# V0_1.net
KiCad netlist of a schematic drawn in EAGLE
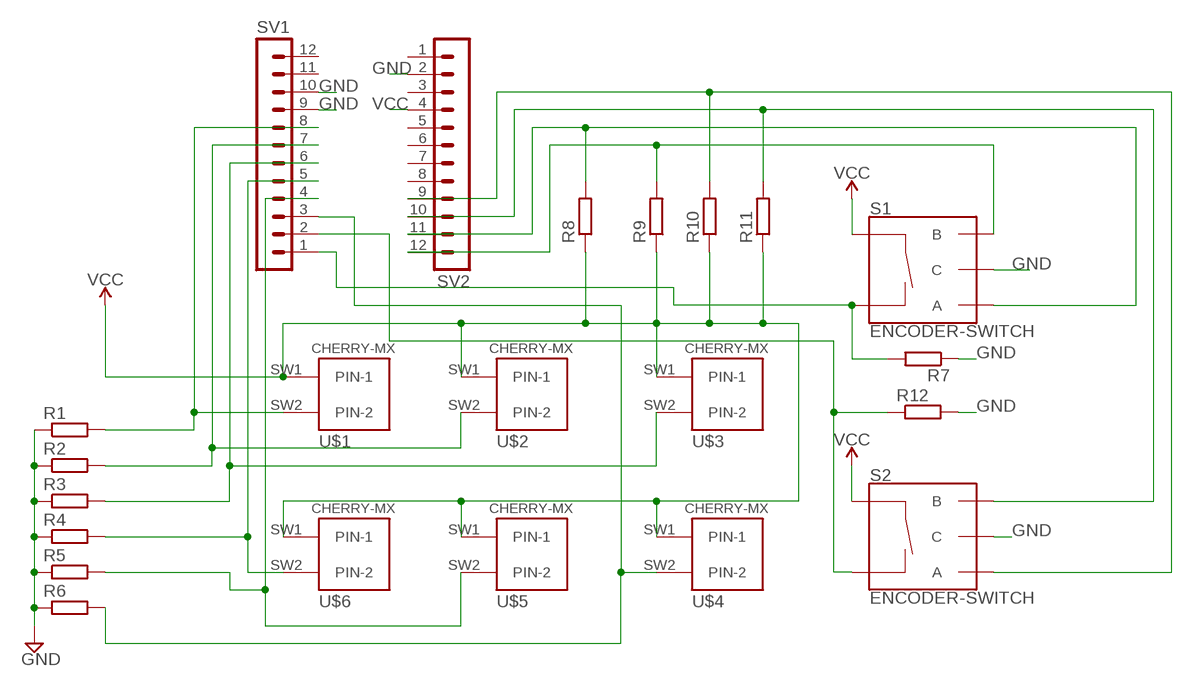
[diagram p0: schematic, sheet 1]

(export (version "E")
  (design (tool "Eeschema 10.0.6"))
  (components
    (comp (ref "R1")
      (value "R-EU_0207/10")
      (footprint "eagle-import:0207_10")
      (libsource (lib "eagle-import") (part "R-EU_0207/10"))
    )
    (comp (ref "R2")
      (value "R-EU_0207/10")
      (footprint "eagle-import:0207_10")
      (libsource (lib "eagle-import") (part "R-EU_0207/10"))
    )
    (comp (ref "R3")
      (value "R-EU_0207/10")
      (footprint "eagle-import:0207_10")
      (libsource (lib "eagle-import") (part "R-EU_0207/10"))
    )
    (comp (ref "R4")
      (value "R-EU_0207/10")
      (footprint "eagle-import:0207_10")
      (libsource (lib "eagle-import") (part "R-EU_0207/10"))
    )
    (comp (ref "R5")
      (value "R-EU_0207/10")
      (footprint "eagle-import:0207_10")
      (libsource (lib "eagle-import") (part "R-EU_0207/10"))
    )
    (comp (ref "R6")
      (value "R-EU_0207/10")
      (footprint "eagle-import:0207_10")
      (libsource (lib "eagle-import") (part "R-EU_0207/10"))
    )
    (comp (ref "R7")
      (value "R-EU_0207/10")
      (footprint "eagle-import:0207_10")
      (libsource (lib "eagle-import") (part "R-EU_0207/10"))
    )
    (comp (ref "R8")
      (value "R-EU_0207/10")
      (footprint "eagle-import:0207_10")
      (libsource (lib "eagle-import") (part "R-EU_0207/10"))
    )
    (comp (ref "R9")
      (value "R-EU_0207/10")
      (footprint "eagle-import:0207_10")
      (libsource (lib "eagle-import") (part "R-EU_0207/10"))
    )
    (comp (ref "R10")
      (value "R-EU_0207/10")
      (footprint "eagle-import:0207_10")
      (libsource (lib "eagle-import") (part "R-EU_0207/10"))
    )
    (comp (ref "R11")
      (value "R-EU_0207/10")
      (footprint "eagle-import:0207_10")
      (libsource (lib "eagle-import") (part "R-EU_0207/10"))
    )
    (comp (ref "R12")
      (value "R-EU_0207/10")
      (footprint "eagle-import:0207_10")
      (libsource (lib "eagle-import") (part "R-EU_0207/10"))
    )
    (comp (ref "S1")
      (value "ENCODER-SWITCH")
      (footprint "eagle-import:ROTARY_ENC_PLAIN")
      (libsource (lib "eagle-import") (part "ENCODER-SWITCH"))
    )
    (comp (ref "S2")
      (value "ENCODER-SWITCH")
      (footprint "eagle-import:ROTARY_ENC_PLAIN")
      (libsource (lib "eagle-import") (part "ENCODER-SWITCH"))
    )
    (comp (ref "SV1")
      (value "MA12-1")
      (footprint "eagle-import:MA12-1")
      (libsource (lib "eagle-import") (part "MA12-1"))
    )
    (comp (ref "SV2")
      (value "MA12-1")
      (footprint "eagle-import:MA12-1")
      (libsource (lib "eagle-import") (part "MA12-1"))
    )
    (comp (ref "U$1")
      (value "CHERRY-MX")
      (footprint "eagle-import:CHERRY-MX")
      (libsource (lib "eagle-import") (part "CHERRY-MX"))
    )
    (comp (ref "U$2")
      (value "CHERRY-MX")
      (footprint "eagle-import:CHERRY-MX")
      (libsource (lib "eagle-import") (part "CHERRY-MX"))
    )
    (comp (ref "U$3")
      (value "CHERRY-MX")
      (footprint "eagle-import:CHERRY-MX")
      (libsource (lib "eagle-import") (part "CHERRY-MX"))
    )
    (comp (ref "U$4")
      (value "CHERRY-MX")
      (footprint "eagle-import:CHERRY-MX")
      (libsource (lib "eagle-import") (part "CHERRY-MX"))
    )
    (comp (ref "U$5")
      (value "CHERRY-MX")
      (footprint "eagle-import:CHERRY-MX")
      (libsource (lib "eagle-import") (part "CHERRY-MX"))
    )
    (comp (ref "U$6")
      (value "CHERRY-MX")
      (footprint "eagle-import:CHERRY-MX")
      (libsource (lib "eagle-import") (part "CHERRY-MX"))
    )
  )
  (nets
    (net (code "1") (name "GND") (class "Default")
      (node (ref "R1") (pin "1") (pinfunction "1_1") (pintype "passive"))
      (node (ref "R12") (pin "2") (pinfunction "2_2") (pintype "passive"))
      (node (ref "R2") (pin "1") (pinfunction "1_1") (pintype "passive"))
      (node (ref "R3") (pin "1") (pinfunction "1_1") (pintype "passive"))
      (node (ref "R4") (pin "1") (pinfunction "1_1") (pintype "passive"))
      (node (ref "R5") (pin "1") (pinfunction "1_1") (pintype "passive"))
      (node (ref "R6") (pin "1") (pinfunction "1_1") (pintype "passive"))
      (node (ref "R7") (pin "1") (pinfunction "1_1") (pintype "passive"))
      (node (ref "S1") (pin "C") (pinfunction "C_C") (pintype "bidirectional"))
      (node (ref "S2") (pin "C") (pinfunction "C_C") (pintype "bidirectional"))
      (node (ref "SV1") (pin "10") (pinfunction "10_10") (pintype "passive"))
      (node (ref "SV1") (pin "9") (pinfunction "9_9") (pintype "passive"))
      (node (ref "SV2") (pin "2") (pinfunction "2_2") (pintype "passive"))
    )
    (net (code "2") (name "Net-(R7-Pad2)") (class "Default")
      (node (ref "R7") (pin "2") (pinfunction "2_2") (pintype "passive"))
      (node (ref "S1") (pin "SW-") (pinfunction "SW-_SW-") (pintype "bidirectional"))
      (node (ref "SV1") (pin "1") (pinfunction "1_1") (pintype "passive"))
    )
    (net (code "3") (name "Net-(R8-Pad2)") (class "Default")
      (node (ref "R8") (pin "2") (pinfunction "2_2") (pintype "passive"))
      (node (ref "S1") (pin "A") (pinfunction "A_A") (pintype "bidirectional"))
      (node (ref "SV2") (pin "11") (pinfunction "11_11") (pintype "passive"))
    )
    (net (code "4") (name "Net-(R9-Pad2)") (class "Default")
      (node (ref "R9") (pin "2") (pinfunction "2_2") (pintype "passive"))
      (node (ref "S1") (pin "B") (pinfunction "B_B") (pintype "bidirectional"))
      (node (ref "SV2") (pin "12") (pinfunction "12_12") (pintype "passive"))
    )
    (net (code "5") (name "Net-(R10-Pad2)") (class "Default")
      (node (ref "R10") (pin "2") (pinfunction "2_2") (pintype "passive"))
      (node (ref "S2") (pin "A") (pinfunction "A_A") (pintype "bidirectional"))
      (node (ref "SV2") (pin "9") (pinfunction "9_9") (pintype "passive"))
    )
    (net (code "6") (name "Net-(R11-Pad2)") (class "Default")
      (node (ref "R11") (pin "2") (pinfunction "2_2") (pintype "passive"))
      (node (ref "S2") (pin "B") (pinfunction "B_B") (pintype "bidirectional"))
      (node (ref "SV2") (pin "10") (pinfunction "10_10") (pintype "passive"))
    )
    (net (code "7") (name "Net-(R12-Pad1)") (class "Default")
      (node (ref "R12") (pin "1") (pinfunction "1_1") (pintype "passive"))
      (node (ref "S2") (pin "SW-") (pinfunction "SW-_SW-") (pintype "bidirectional"))
      (node (ref "SV1") (pin "2") (pinfunction "2_2") (pintype "passive"))
    )
    (net (code "8") (name "Net-(U$1-PIN-2)") (class "Default")
      (node (ref "R1") (pin "2") (pinfunction "2_2") (pintype "passive"))
      (node (ref "SV1") (pin "8") (pinfunction "8_8") (pintype "passive"))
      (node (ref "U$1") (pin "SW2") (pinfunction "PIN-2_SW2") (pintype "bidirectional"))
    )
    (net (code "9") (name "Net-(U$2-PIN-2)") (class "Default")
      (node (ref "R2") (pin "2") (pinfunction "2_2") (pintype "passive"))
      (node (ref "SV1") (pin "7") (pinfunction "7_7") (pintype "passive"))
      (node (ref "U$2") (pin "SW2") (pinfunction "PIN-2_SW2") (pintype "bidirectional"))
    )
    (net (code "10") (name "Net-(U$3-PIN-2)") (class "Default")
      (node (ref "R3") (pin "2") (pinfunction "2_2") (pintype "passive"))
      (node (ref "SV1") (pin "6") (pinfunction "6_6") (pintype "passive"))
      (node (ref "U$3") (pin "SW2") (pinfunction "PIN-2_SW2") (pintype "bidirectional"))
    )
    (net (code "11") (name "Net-(U$4-PIN-2)") (class "Default")
      (node (ref "R6") (pin "2") (pinfunction "2_2") (pintype "passive"))
      (node (ref "SV1") (pin "3") (pinfunction "3_3") (pintype "passive"))
      (node (ref "U$4") (pin "SW2") (pinfunction "PIN-2_SW2") (pintype "bidirectional"))
    )
    (net (code "12") (name "Net-(U$5-PIN-2)") (class "Default")
      (node (ref "R5") (pin "2") (pinfunction "2_2") (pintype "passive"))
      (node (ref "SV1") (pin "4") (pinfunction "4_4") (pintype "passive"))
      (node (ref "U$5") (pin "SW2") (pinfunction "PIN-2_SW2") (pintype "bidirectional"))
    )
    (net (code "13") (name "Net-(U$6-PIN-2)") (class "Default")
      (node (ref "R4") (pin "2") (pinfunction "2_2") (pintype "passive"))
      (node (ref "SV1") (pin "5") (pinfunction "5_5") (pintype "passive"))
      (node (ref "U$6") (pin "SW2") (pinfunction "PIN-2_SW2") (pintype "bidirectional"))
    )
    (net (code "14") (name "VCC") (class "Default")
      (node (ref "R10") (pin "1") (pinfunction "1_1") (pintype "passive"))
      (node (ref "R11") (pin "1") (pinfunction "1_1") (pintype "passive"))
      (node (ref "R8") (pin "1") (pinfunction "1_1") (pintype "passive"))
      (node (ref "R9") (pin "1") (pinfunction "1_1") (pintype "passive"))
      (node (ref "S1") (pin "SW+") (pinfunction "SW+_SW+") (pintype "bidirectional"))
      (node (ref "S2") (pin "SW+") (pinfunction "SW+_SW+") (pintype "bidirectional"))
      (node (ref "SV2") (pin "4") (pinfunction "4_4") (pintype "passive"))
      (node (ref "U$1") (pin "SW1") (pinfunction "PIN-1_SW1") (pintype "bidirectional"))
      (node (ref "U$2") (pin "SW1") (pinfunction "PIN-1_SW1") (pintype "bidirectional"))
      (node (ref "U$3") (pin "SW1") (pinfunction "PIN-1_SW1") (pintype "bidirectional"))
      (node (ref "U$4") (pin "SW1") (pinfunction "PIN-1_SW1") (pintype "bidirectional"))
      (node (ref "U$5") (pin "SW1") (pinfunction "PIN-1_SW1") (pintype "bidirectional"))
      (node (ref "U$6") (pin "SW1") (pinfunction "PIN-1_SW1") (pintype "bidirectional"))
    )
    (net (code "15") (name "unconnected-(SV1-Pad11)") (class "Default")
      (node (ref "SV1") (pin "11") (pinfunction "11_11") (pintype "passive"))
    )
    (net (code "16") (name "unconnected-(SV1-Pad12)") (class "Default")
      (node (ref "SV1") (pin "12") (pinfunction "12_12") (pintype "passive"))
    )
    (net (code "17") (name "unconnected-(SV2-Pad1)") (class "Default")
      (node (ref "SV2") (pin "1") (pinfunction "1_1") (pintype "passive"))
    )
    (net (code "18") (name "unconnected-(SV2-Pad3)") (class "Default")
      (node (ref "SV2") (pin "3") (pinfunction "3_3") (pintype "passive"))
    )
    (net (code "19") (name "unconnected-(SV2-Pad5)") (class "Default")
      (node (ref "SV2") (pin "5") (pinfunction "5_5") (pintype "passive"))
    )
    (net (code "20") (name "unconnected-(SV2-Pad6)") (class "Default")
      (node (ref "SV2") (pin "6") (pinfunction "6_6") (pintype "passive"))
    )
    (net (code "21") (name "unconnected-(SV2-Pad7)") (class "Default")
      (node (ref "SV2") (pin "7") (pinfunction "7_7") (pintype "passive"))
    )
    (net (code "22") (name "unconnected-(SV2-Pad8)") (class "Default")
      (node (ref "SV2") (pin "8") (pinfunction "8_8") (pintype "passive"))
    )
  )
)
